# Sheet_ConnectA10.net
KiCad netlist of a schematic drawn in Altium Designer
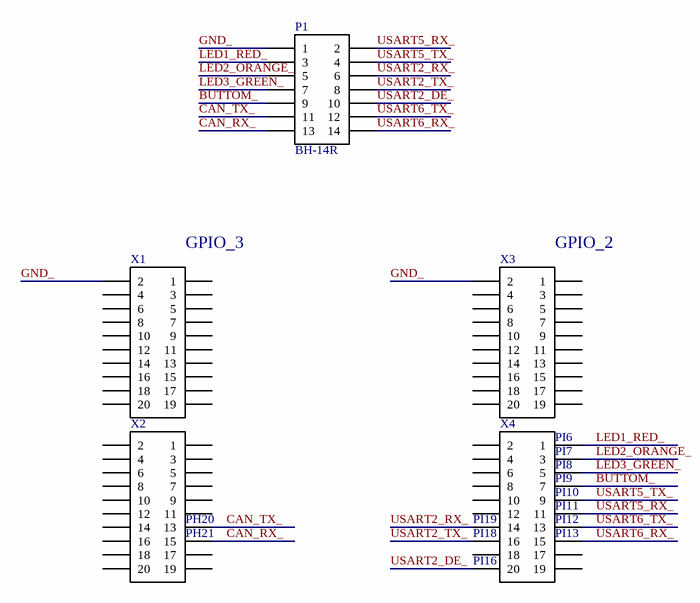
[diagram p0: Sheet_ConnectA10.SchDoc]

(export (version "E")
  (design (tool "Eeschema 10.0.6"))
  (components
    (comp (ref "P1")
      (value "BH-14R")
      (footprint "BH-14R")
      (description "IDC/BH")
      (fields (field (name "PUBLISHER") "Altium Limited"))
      (libsource (lib "Connect") (part "BH-14"))
    )
    (comp (ref "X1")
      (value "PBD2-20")
      (footprint "PBD2-1.27-20-SMD")
      (description "Header, 20-Pin")
      (libsource (lib "Connect") (part "PBD2-20"))
    )
    (comp (ref "X2")
      (value "PBD2-20")
      (footprint "PBD2-1.27-20-SMD")
      (description "Header, 20-Pin")
      (libsource (lib "Connect") (part "PBD2-20"))
    )
    (comp (ref "X3")
      (value "PBD2-20")
      (footprint "PBD2-1.27-20-SMD")
      (description "Header, 20-Pin")
      (libsource (lib "Connect") (part "PBD2-20"))
    )
    (comp (ref "X4")
      (value "PBD2-20")
      (footprint "PBD2-1.27-20-SMD")
      (description "Header, 20-Pin")
      (libsource (lib "Connect") (part "PBD2-20"))
    )
  )
  (nets
    (net (code "1") (name "/BUTTOM_") (class "Default")
      (node (ref "P1") (pin "9") (pinfunction "9_9") (pintype "passive"))
      (node (ref "X4") (pin "7") (pinfunction "7_7") (pintype "passive"))
    )
    (net (code "2") (name "/CAN_RX_") (class "Default")
      (node (ref "P1") (pin "13") (pinfunction "13_13") (pintype "passive"))
      (node (ref "X2") (pin "15") (pinfunction "15_15") (pintype "passive"))
    )
    (net (code "3") (name "/CAN_TX_") (class "Default")
      (node (ref "P1") (pin "11") (pinfunction "11_11") (pintype "passive"))
      (node (ref "X2") (pin "13") (pinfunction "13_13") (pintype "passive"))
    )
    (net (code "4") (name "/GND_") (class "Default")
      (node (ref "P1") (pin "1") (pinfunction "1_1") (pintype "passive"))
      (node (ref "X1") (pin "2") (pinfunction "2_2") (pintype "passive"))
      (node (ref "X3") (pin "2") (pinfunction "2_2") (pintype "passive"))
    )
    (net (code "5") (name "/LED1_RED_") (class "Default")
      (node (ref "P1") (pin "3") (pinfunction "3_3") (pintype "passive"))
      (node (ref "X4") (pin "1") (pinfunction "1_1") (pintype "passive"))
    )
    (net (code "6") (name "/LED2_ORANGE_") (class "Default")
      (node (ref "P1") (pin "5") (pinfunction "5_5") (pintype "passive"))
      (node (ref "X4") (pin "3") (pinfunction "3_3") (pintype "passive"))
    )
    (net (code "7") (name "/LED3_GREEN_") (class "Default")
      (node (ref "P1") (pin "7") (pinfunction "7_7") (pintype "passive"))
      (node (ref "X4") (pin "5") (pinfunction "5_5") (pintype "passive"))
    )
    (net (code "8") (name "/USART2_DE_") (class "Default")
      (node (ref "P1") (pin "10") (pinfunction "10_10") (pintype "passive"))
      (node (ref "X4") (pin "20") (pinfunction "20_20") (pintype "passive"))
    )
    (net (code "9") (name "/USART2_RX_") (class "Default")
      (node (ref "P1") (pin "6") (pinfunction "6_6") (pintype "passive"))
      (node (ref "X4") (pin "14") (pinfunction "14_14") (pintype "passive"))
    )
    (net (code "10") (name "/USART2_TX_") (class "Default")
      (node (ref "P1") (pin "8") (pinfunction "8_8") (pintype "passive"))
      (node (ref "X4") (pin "16") (pinfunction "16_16") (pintype "passive"))
    )
    (net (code "11") (name "/USART5_RX_") (class "Default")
      (node (ref "P1") (pin "2") (pinfunction "2_2") (pintype "passive"))
      (node (ref "X4") (pin "11") (pinfunction "11_11") (pintype "passive"))
    )
    (net (code "12") (name "/USART5_TX_") (class "Default")
      (node (ref "P1") (pin "4") (pinfunction "4_4") (pintype "passive"))
      (node (ref "X4") (pin "9") (pinfunction "9_9") (pintype "passive"))
    )
    (net (code "13") (name "/USART6_RX_") (class "Default")
      (node (ref "P1") (pin "14") (pinfunction "14_14") (pintype "passive"))
      (node (ref "X4") (pin "15") (pinfunction "15_15") (pintype "passive"))
    )
    (net (code "14") (name "/USART6_TX_") (class "Default")
      (node (ref "P1") (pin "12") (pinfunction "12_12") (pintype "passive"))
      (node (ref "X4") (pin "13") (pinfunction "13_13") (pintype "passive"))
    )
    (net (code "15") (name "unconnected-(X1-Pad1)") (class "Default")
      (node (ref "X1") (pin "1") (pinfunction "1_1") (pintype "passive"))
    )
    (net (code "16") (name "unconnected-(X1-Pad3)") (class "Default")
      (node (ref "X1") (pin "3") (pinfunction "3_3") (pintype "passive"))
    )
    (net (code "17") (name "unconnected-(X1-Pad4)") (class "Default")
      (node (ref "X1") (pin "4") (pinfunction "4_4") (pintype "passive"))
    )
    (net (code "18") (name "unconnected-(X1-Pad5)") (class "Default")
      (node (ref "X1") (pin "5") (pinfunction "5_5") (pintype "passive"))
    )
    (net (code "19") (name "unconnected-(X1-Pad6)") (class "Default")
      (node (ref "X1") (pin "6") (pinfunction "6_6") (pintype "passive"))
    )
    (net (code "20") (name "unconnected-(X1-Pad7)") (class "Default")
      (node (ref "X1") (pin "7") (pinfunction "7_7") (pintype "passive"))
    )
    (net (code "21") (name "unconnected-(X1-Pad8)") (class "Default")
      (node (ref "X1") (pin "8") (pinfunction "8_8") (pintype "passive"))
    )
    (net (code "22") (name "unconnected-(X1-Pad9)") (class "Default")
      (node (ref "X1") (pin "9") (pinfunction "9_9") (pintype "passive"))
    )
    (net (code "23") (name "unconnected-(X1-Pad10)") (class "Default")
      (node (ref "X1") (pin "10") (pinfunction "10_10") (pintype "passive"))
    )
    (net (code "24") (name "unconnected-(X1-Pad11)") (class "Default")
      (node (ref "X1") (pin "11") (pinfunction "11_11") (pintype "passive"))
    )
    (net (code "25") (name "unconnected-(X1-Pad12)") (class "Default")
      (node (ref "X1") (pin "12") (pinfunction "12_12") (pintype "passive"))
    )
    (net (code "26") (name "unconnected-(X1-Pad13)") (class "Default")
      (node (ref "X1") (pin "13") (pinfunction "13_13") (pintype "passive"))
    )
    (net (code "27") (name "unconnected-(X1-Pad14)") (class "Default")
      (node (ref "X1") (pin "14") (pinfunction "14_14") (pintype "passive"))
    )
    (net (code "28") (name "unconnected-(X1-Pad15)") (class "Default")
      (node (ref "X1") (pin "15") (pinfunction "15_15") (pintype "passive"))
    )
    (net (code "29") (name "unconnected-(X1-Pad16)") (class "Default")
      (node (ref "X1") (pin "16") (pinfunction "16_16") (pintype "passive"))
    )
    (net (code "30") (name "unconnected-(X1-Pad17)") (class "Default")
      (node (ref "X1") (pin "17") (pinfunction "17_17") (pintype "passive"))
    )
    (net (code "31") (name "unconnected-(X1-Pad18)") (class "Default")
      (node (ref "X1") (pin "18") (pinfunction "18_18") (pintype "passive"))
    )
    (net (code "32") (name "unconnected-(X1-Pad19)") (class "Default")
      (node (ref "X1") (pin "19") (pinfunction "19_19") (pintype "passive"))
    )
    (net (code "33") (name "unconnected-(X1-Pad20)") (class "Default")
      (node (ref "X1") (pin "20") (pinfunction "20_20") (pintype "passive"))
    )
    (net (code "34") (name "unconnected-(X2-Pad1)") (class "Default")
      (node (ref "X2") (pin "1") (pinfunction "1_1") (pintype "passive"))
    )
    (net (code "35") (name "unconnected-(X2-Pad2)") (class "Default")
      (node (ref "X2") (pin "2") (pinfunction "2_2") (pintype "passive"))
    )
    (net (code "36") (name "unconnected-(X2-Pad3)") (class "Default")
      (node (ref "X2") (pin "3") (pinfunction "3_3") (pintype "passive"))
    )
    (net (code "37") (name "unconnected-(X2-Pad4)") (class "Default")
      (node (ref "X2") (pin "4") (pinfunction "4_4") (pintype "passive"))
    )
    (net (code "38") (name "unconnected-(X2-Pad5)") (class "Default")
      (node (ref "X2") (pin "5") (pinfunction "5_5") (pintype "passive"))
    )
    (net (code "39") (name "unconnected-(X2-Pad6)") (class "Default")
      (node (ref "X2") (pin "6") (pinfunction "6_6") (pintype "passive"))
    )
    (net (code "40") (name "unconnected-(X2-Pad7)") (class "Default")
      (node (ref "X2") (pin "7") (pinfunction "7_7") (pintype "passive"))
    )
    (net (code "41") (name "unconnected-(X2-Pad8)") (class "Default")
      (node (ref "X2") (pin "8") (pinfunction "8_8") (pintype "passive"))
    )
    (net (code "42") (name "unconnected-(X2-Pad9)") (class "Default")
      (node (ref "X2") (pin "9") (pinfunction "9_9") (pintype "passive"))
    )
    (net (code "43") (name "unconnected-(X2-Pad10)") (class "Default")
      (node (ref "X2") (pin "10") (pinfunction "10_10") (pintype "passive"))
    )
    (net (code "44") (name "unconnected-(X2-Pad11)") (class "Default")
      (node (ref "X2") (pin "11") (pinfunction "11_11") (pintype "passive"))
    )
    (net (code "45") (name "unconnected-(X2-Pad12)") (class "Default")
      (node (ref "X2") (pin "12") (pinfunction "12_12") (pintype "passive"))
    )
    (net (code "46") (name "unconnected-(X2-Pad14)") (class "Default")
      (node (ref "X2") (pin "14") (pinfunction "14_14") (pintype "passive"))
    )
    (net (code "47") (name "unconnected-(X2-Pad16)") (class "Default")
      (node (ref "X2") (pin "16") (pinfunction "16_16") (pintype "passive"))
    )
    (net (code "48") (name "unconnected-(X2-Pad17)") (class "Default")
      (node (ref "X2") (pin "17") (pinfunction "17_17") (pintype "passive"))
    )
    (net (code "49") (name "unconnected-(X2-Pad18)") (class "Default")
      (node (ref "X2") (pin "18") (pinfunction "18_18") (pintype "passive"))
    )
    (net (code "50") (name "unconnected-(X2-Pad19)") (class "Default")
      (node (ref "X2") (pin "19") (pinfunction "19_19") (pintype "passive"))
    )
    (net (code "51") (name "unconnected-(X2-Pad20)") (class "Default")
      (node (ref "X2") (pin "20") (pinfunction "20_20") (pintype "passive"))
    )
    (net (code "52") (name "unconnected-(X3-Pad1)") (class "Default")
      (node (ref "X3") (pin "1") (pinfunction "1_1") (pintype "passive"))
    )
    (net (code "53") (name "unconnected-(X3-Pad3)") (class "Default")
      (node (ref "X3") (pin "3") (pinfunction "3_3") (pintype "passive"))
    )
    (net (code "54") (name "unconnected-(X3-Pad4)") (class "Default")
      (node (ref "X3") (pin "4") (pinfunction "4_4") (pintype "passive"))
    )
    (net (code "55") (name "unconnected-(X3-Pad5)") (class "Default")
      (node (ref "X3") (pin "5") (pinfunction "5_5") (pintype "passive"))
    )
    (net (code "56") (name "unconnected-(X3-Pad6)") (class "Default")
      (node (ref "X3") (pin "6") (pinfunction "6_6") (pintype "passive"))
    )
    (net (code "57") (name "unconnected-(X3-Pad7)") (class "Default")
      (node (ref "X3") (pin "7") (pinfunction "7_7") (pintype "passive"))
    )
    (net (code "58") (name "unconnected-(X3-Pad8)") (class "Default")
      (node (ref "X3") (pin "8") (pinfunction "8_8") (pintype "passive"))
    )
    (net (code "59") (name "unconnected-(X3-Pad9)") (class "Default")
      (node (ref "X3") (pin "9") (pinfunction "9_9") (pintype "passive"))
    )
    (net (code "60") (name "unconnected-(X3-Pad10)") (class "Default")
      (node (ref "X3") (pin "10") (pinfunction "10_10") (pintype "passive"))
    )
    (net (code "61") (name "unconnected-(X3-Pad11)") (class "Default")
      (node (ref "X3") (pin "11") (pinfunction "11_11") (pintype "passive"))
    )
    (net (code "62") (name "unconnected-(X3-Pad12)") (class "Default")
      (node (ref "X3") (pin "12") (pinfunction "12_12") (pintype "passive"))
    )
    (net (code "63") (name "unconnected-(X3-Pad13)") (class "Default")
      (node (ref "X3") (pin "13") (pinfunction "13_13") (pintype "passive"))
    )
    (net (code "64") (name "unconnected-(X3-Pad14)") (class "Default")
      (node (ref "X3") (pin "14") (pinfunction "14_14") (pintype "passive"))
    )
    (net (code "65") (name "unconnected-(X3-Pad15)") (class "Default")
      (node (ref "X3") (pin "15") (pinfunction "15_15") (pintype "passive"))
    )
    (net (code "66") (name "unconnected-(X3-Pad16)") (class "Default")
      (node (ref "X3") (pin "16") (pinfunction "16_16") (pintype "passive"))
    )
    (net (code "67") (name "unconnected-(X3-Pad17)") (class "Default")
      (node (ref "X3") (pin "17") (pinfunction "17_17") (pintype "passive"))
    )
    (net (code "68") (name "unconnected-(X3-Pad18)") (class "Default")
      (node (ref "X3") (pin "18") (pinfunction "18_18") (pintype "passive"))
    )
    (net (code "69") (name "unconnected-(X3-Pad19)") (class "Default")
      (node (ref "X3") (pin "19") (pinfunction "19_19") (pintype "passive"))
    )
    (net (code "70") (name "unconnected-(X3-Pad20)") (class "Default")
      (node (ref "X3") (pin "20") (pinfunction "20_20") (pintype "passive"))
    )
    (net (code "71") (name "unconnected-(X4-Pad2)") (class "Default")
      (node (ref "X4") (pin "2") (pinfunction "2_2") (pintype "passive"))
    )
    (net (code "72") (name "unconnected-(X4-Pad4)") (class "Default")
      (node (ref "X4") (pin "4") (pinfunction "4_4") (pintype "passive"))
    )
    (net (code "73") (name "unconnected-(X4-Pad6)") (class "Default")
      (node (ref "X4") (pin "6") (pinfunction "6_6") (pintype "passive"))
    )
    (net (code "74") (name "unconnected-(X4-Pad8)") (class "Default")
      (node (ref "X4") (pin "8") (pinfunction "8_8") (pintype "passive"))
    )
    (net (code "75") (name "unconnected-(X4-Pad10)") (class "Default")
      (node (ref "X4") (pin "10") (pinfunction "10_10") (pintype "passive"))
    )
    (net (code "76") (name "unconnected-(X4-Pad12)") (class "Default")
      (node (ref "X4") (pin "12") (pinfunction "12_12") (pintype "passive"))
    )
    (net (code "77") (name "unconnected-(X4-Pad17)") (class "Default")
      (node (ref "X4") (pin "17") (pinfunction "17_17") (pintype "passive"))
    )
    (net (code "78") (name "unconnected-(X4-Pad18)") (class "Default")
      (node (ref "X4") (pin "18") (pinfunction "18_18") (pintype "passive"))
    )
    (net (code "79") (name "unconnected-(X4-Pad19)") (class "Default")
      (node (ref "X4") (pin "19") (pinfunction "19_19") (pintype "passive"))
    )
  )
)
